# Relay_Breakout.net
KiCad netlist of a schematic drawn in EAGLE
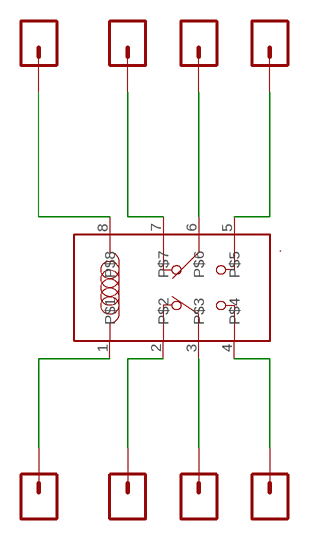
[diagram p0: schematic, sheet 1]

(export (version "E")
  (design (tool "Eeschema 10.0.6"))
  (components
    (comp (ref ".")
      (value "IM21IM21-THT")
      (footprint "eagle-import:THT")
      (libsource (lib "eagle-import") (part "IM21IM21-THT"))
    )
    (comp (ref "JP3")
      (value "M01PTH")
      (footprint "eagle-import:1X01")
      (libsource (lib "eagle-import") (part "M01PTH"))
    )
    (comp (ref "JP4")
      (value "M01PTH")
      (footprint "eagle-import:1X01")
      (libsource (lib "eagle-import") (part "M01PTH"))
    )
    (comp (ref "JP5")
      (value "M01PTH")
      (footprint "eagle-import:1X01")
      (libsource (lib "eagle-import") (part "M01PTH"))
    )
    (comp (ref "JP6")
      (value "M01PTH")
      (footprint "eagle-import:1X01")
      (libsource (lib "eagle-import") (part "M01PTH"))
    )
    (comp (ref "JP7")
      (value "M01PTH")
      (footprint "eagle-import:1X01")
      (libsource (lib "eagle-import") (part "M01PTH"))
    )
    (comp (ref "JP8")
      (value "M01PTH")
      (footprint "eagle-import:1X01")
      (libsource (lib "eagle-import") (part "M01PTH"))
    )
    (comp (ref "JP9")
      (value "M01PTH")
      (footprint "eagle-import:1X01")
      (libsource (lib "eagle-import") (part "M01PTH"))
    )
    (comp (ref "JP10")
      (value "M01PTH")
      (footprint "eagle-import:1X01")
      (libsource (lib "eagle-import") (part "M01PTH"))
    )
  )
  (nets
    (net (code "1") (name "Net-(.-P$1)") (class "Default")
      (node (ref ".") (pin "1") (pinfunction "P$1_1") (pintype "bidirectional"))
      (node (ref "JP3") (pin "1") (pinfunction "1_1") (pintype "passive"))
    )
    (net (code "2") (name "Net-(.-P$2)") (class "Default")
      (node (ref ".") (pin "2") (pinfunction "P$2_2") (pintype "bidirectional"))
      (node (ref "JP4") (pin "1") (pinfunction "1_1") (pintype "passive"))
    )
    (net (code "3") (name "Net-(.-P$3)") (class "Default")
      (node (ref ".") (pin "3") (pinfunction "P$3_3") (pintype "bidirectional"))
      (node (ref "JP5") (pin "1") (pinfunction "1_1") (pintype "passive"))
    )
    (net (code "4") (name "Net-(.-P$4)") (class "Default")
      (node (ref ".") (pin "4") (pinfunction "P$4_4") (pintype "bidirectional"))
      (node (ref "JP6") (pin "1") (pinfunction "1_1") (pintype "passive"))
    )
    (net (code "5") (name "Net-(.-P$5)") (class "Default")
      (node (ref ".") (pin "5") (pinfunction "P$5_5") (pintype "bidirectional"))
      (node (ref "JP7") (pin "1") (pinfunction "1_1") (pintype "passive"))
    )
    (net (code "6") (name "Net-(.-P$6)") (class "Default")
      (node (ref ".") (pin "6") (pinfunction "P$6_6") (pintype "bidirectional"))
      (node (ref "JP8") (pin "1") (pinfunction "1_1") (pintype "passive"))
    )
    (net (code "7") (name "Net-(.-P$7)") (class "Default")
      (node (ref ".") (pin "7") (pinfunction "P$7_7") (pintype "bidirectional"))
      (node (ref "JP9") (pin "1") (pinfunction "1_1") (pintype "passive"))
    )
    (net (code "8") (name "Net-(.-P$8)") (class "Default")
      (node (ref ".") (pin "8") (pinfunction "P$8_8") (pintype "bidirectional"))
      (node (ref "JP10") (pin "1") (pinfunction "1_1") (pintype "passive"))
    )
  )
)
